# PCB-ENCODER3.net
KiCad netlist of a schematic drawn in EAGLE
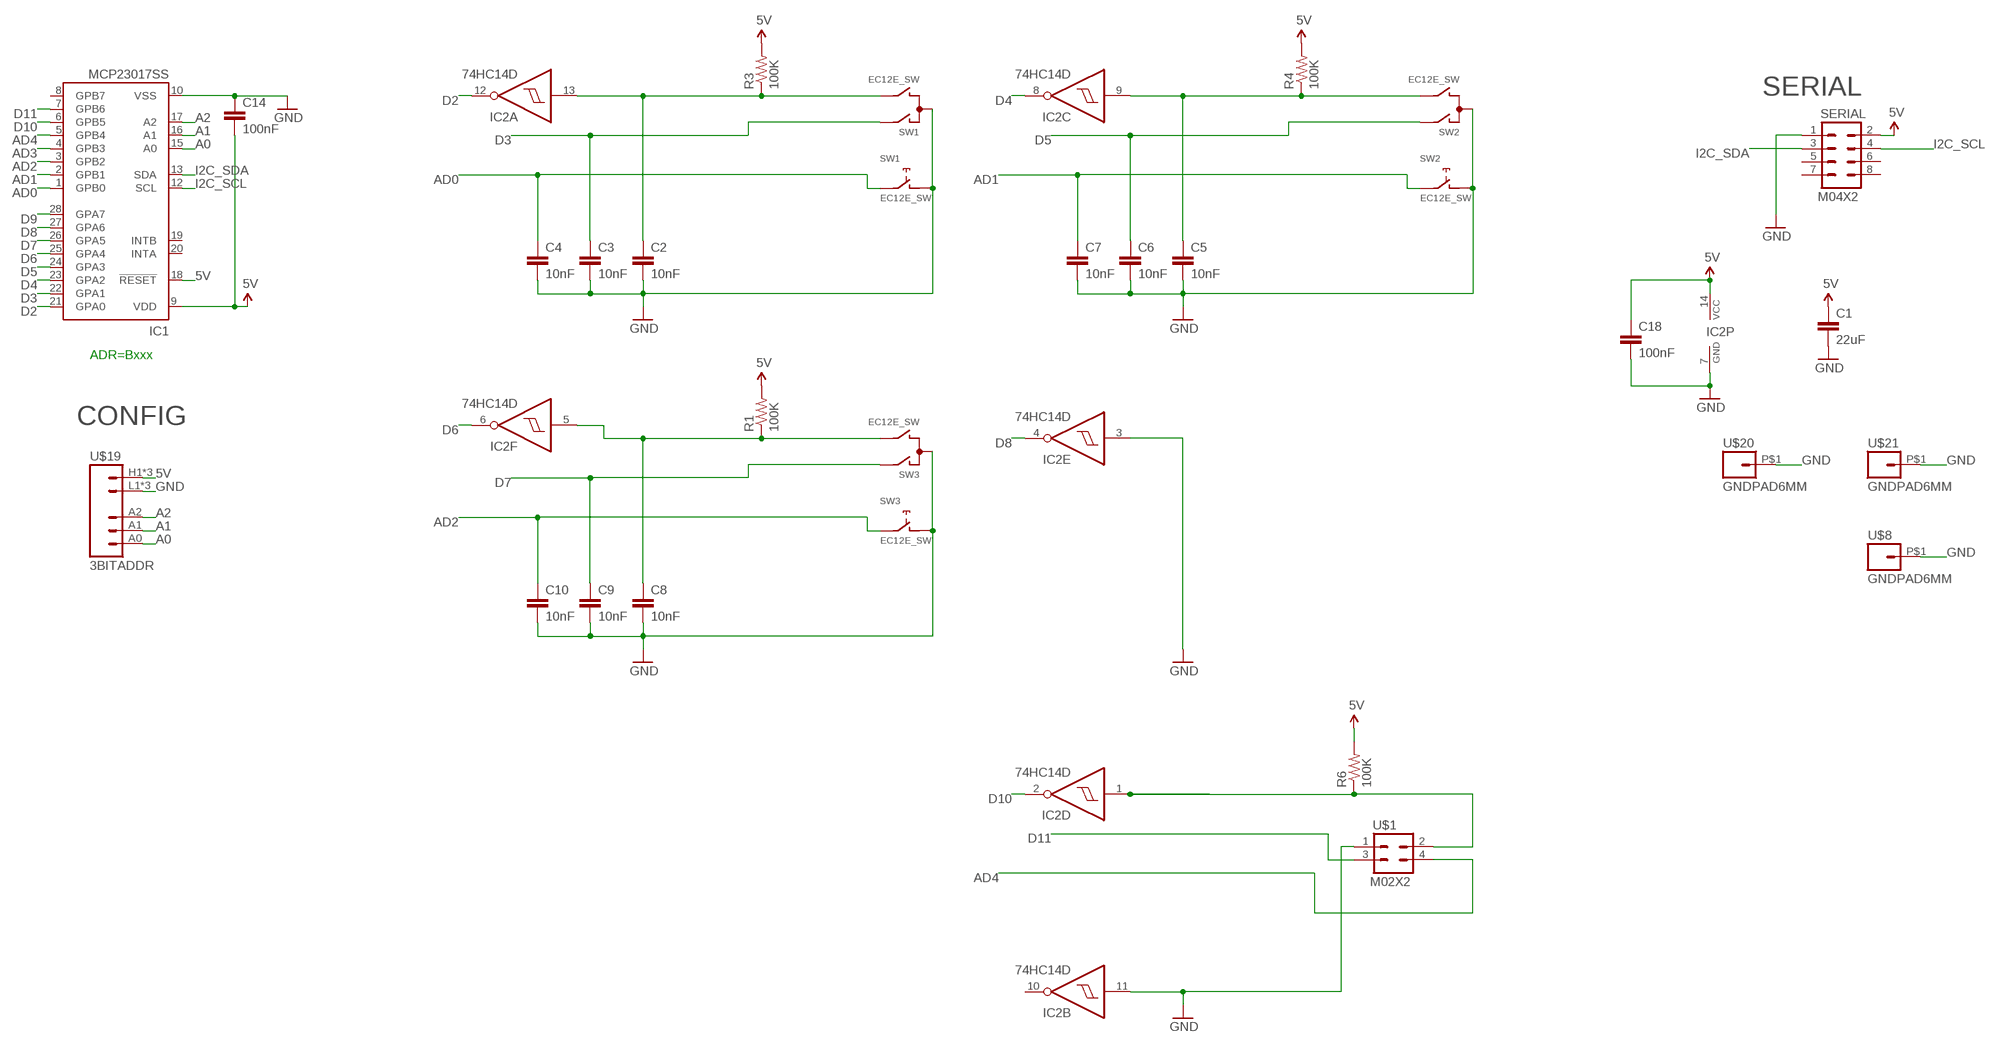
[diagram p0: schematic, sheet 1]

(export (version "E")
  (design (tool "Eeschema 10.0.6"))
  (components
    (comp (ref "C1")
      (value "22uF")
      (footprint "eagle-import:0805")
      (libsource (lib "eagle-import") (part "CAP0805"))
    )
    (comp (ref "C2")
      (value "10nF")
      (footprint "eagle-import:0603-CAP")
      (libsource (lib "eagle-import") (part "CAP0603-CAP"))
    )
    (comp (ref "C3")
      (value "10nF")
      (footprint "eagle-import:0603-CAP")
      (libsource (lib "eagle-import") (part "CAP0603-CAP"))
    )
    (comp (ref "C4")
      (value "10nF")
      (footprint "eagle-import:0603-CAP")
      (libsource (lib "eagle-import") (part "CAP0603-CAP"))
    )
    (comp (ref "C5")
      (value "10nF")
      (footprint "eagle-import:0603-CAP")
      (libsource (lib "eagle-import") (part "CAP0603-CAP"))
    )
    (comp (ref "C6")
      (value "10nF")
      (footprint "eagle-import:0603-CAP")
      (libsource (lib "eagle-import") (part "CAP0603-CAP"))
    )
    (comp (ref "C7")
      (value "10nF")
      (footprint "eagle-import:0603-CAP")
      (libsource (lib "eagle-import") (part "CAP0603-CAP"))
    )
    (comp (ref "C8")
      (value "10nF")
      (footprint "eagle-import:0603-CAP")
      (libsource (lib "eagle-import") (part "CAP0603-CAP"))
    )
    (comp (ref "C9")
      (value "10nF")
      (footprint "eagle-import:0603-CAP")
      (libsource (lib "eagle-import") (part "CAP0603-CAP"))
    )
    (comp (ref "C10")
      (value "10nF")
      (footprint "eagle-import:0603-CAP")
      (libsource (lib "eagle-import") (part "CAP0603-CAP"))
    )
    (comp (ref "C14")
      (value "100nF")
      (footprint "eagle-import:0603-CAP")
      (libsource (lib "eagle-import") (part "CAP0603-CAP"))
    )
    (comp (ref "C18")
      (value "100nF")
      (footprint "eagle-import:0603-CAP")
      (libsource (lib "eagle-import") (part "CAP0603-CAP"))
    )
    (comp (ref "IC1")
      (value "MCP23017SS")
      (footprint "eagle-import:SSOP28")
      (fields
        (field (name "MF") "MICROCHIP")
        (field (name "MPN") "MCP23017-E/SS")
        (field (name "MPN_1") "MCP23017-E/SS")
        (field (name "OC_FARNELL") "1467674")
        (field (name "OC_NEWARK") "31K2960")
      )
      (libsource (lib "eagle-import") (part "MCP23017SS"))
    )
    (comp (ref "IC2")
      (value "74HC14D")
      (footprint "eagle-import:SO14")
      (libsource (lib "eagle-import") (part "7414DHC"))
    )
    (comp (ref "R1")
      (value "100K")
      (footprint "eagle-import:0603-RES")
      (libsource (lib "eagle-import") (part "RESISTOR0603-RES"))
    )
    (comp (ref "R3")
      (value "100K")
      (footprint "eagle-import:0603-RES")
      (libsource (lib "eagle-import") (part "RESISTOR0603-RES"))
    )
    (comp (ref "R4")
      (value "100K")
      (footprint "eagle-import:0603-RES")
      (libsource (lib "eagle-import") (part "RESISTOR0603-RES"))
    )
    (comp (ref "R6")
      (value "100K")
      (footprint "eagle-import:0603-RES")
      (libsource (lib "eagle-import") (part "RESISTOR0603-RES"))
    )
    (comp (ref "SERIAL")
      (value "M04X2")
      (footprint "eagle-import:2X4")
      (libsource (lib "eagle-import") (part "M04X2"))
    )
    (comp (ref "SW1")
      (value "EC12E_SW")
      (footprint "eagle-import:ALPS_EC12E_SW")
      (fields (field (name "MPN") "EC12E2424407"))
      (libsource (lib "eagle-import") (part "EC12E_SW"))
    )
    (comp (ref "SW2")
      (value "EC12E_SW")
      (footprint "eagle-import:ALPS_EC12E_SW")
      (fields (field (name "MPN") "EC12E2424407"))
      (libsource (lib "eagle-import") (part "EC12E_SW"))
    )
    (comp (ref "SW3")
      (value "EC12E_SW")
      (footprint "eagle-import:ALPS_EC12E_SW")
      (fields (field (name "MPN") "EC12E2424407"))
      (libsource (lib "eagle-import") (part "EC12E_SW"))
    )
    (comp (ref "U$1")
      (value "M02X2")
      (footprint "eagle-import:2X2")
      (libsource (lib "eagle-import") (part "M02X2"))
    )
    (comp (ref "U$8")
      (value "GNDPAD6MM")
      (footprint "eagle-import:3.2MMPAD6MM")
      (libsource (lib "eagle-import") (part "GNDPAD6MM"))
    )
    (comp (ref "U$19")
      (value "3BITADDR")
      (footprint "eagle-import:3BITADDR")
      (libsource (lib "eagle-import") (part "3BITADDR"))
    )
    (comp (ref "U$20")
      (value "GNDPAD6MM")
      (footprint "eagle-import:3.2MMPAD6MM")
      (libsource (lib "eagle-import") (part "GNDPAD6MM"))
    )
    (comp (ref "U$21")
      (value "GNDPAD6MM")
      (footprint "eagle-import:3.2MMPAD6MM")
      (libsource (lib "eagle-import") (part "GNDPAD6MM"))
    )
  )
  (nets
    (net (code "1") (name "/A0") (class "Default")
      (node (ref "IC1") (pin "15") (pinfunction "A0_15") (pintype "input"))
      (node (ref "U$19") (pin "A0") (pinfunction "A0_A0") (pintype "passive"))
    )
    (net (code "2") (name "/A1") (class "Default")
      (node (ref "IC1") (pin "16") (pinfunction "A1_16") (pintype "input"))
      (node (ref "U$19") (pin "A1") (pinfunction "A1_A1") (pintype "passive"))
    )
    (net (code "3") (name "/A2") (class "Default")
      (node (ref "IC1") (pin "17") (pinfunction "A2_17") (pintype "input"))
      (node (ref "U$19") (pin "A2") (pinfunction "A2_A2") (pintype "passive"))
    )
    (net (code "4") (name "/AD0") (class "Default")
      (node (ref "C4") (pin "1") (pinfunction "1_1") (pintype "passive"))
      (node (ref "IC1") (pin "1") (pinfunction "GPB0_1") (pintype "bidirectional"))
      (node (ref "SW1") (pin "E") (pinfunction "2_E") (pintype "passive"))
    )
    (net (code "5") (name "/AD1") (class "Default")
      (node (ref "C7") (pin "1") (pinfunction "1_1") (pintype "passive"))
      (node (ref "IC1") (pin "2") (pinfunction "GPB1_2") (pintype "bidirectional"))
      (node (ref "SW2") (pin "E") (pinfunction "2_E") (pintype "passive"))
    )
    (net (code "6") (name "/AD2") (class "Default")
      (node (ref "C10") (pin "1") (pinfunction "1_1") (pintype "passive"))
      (node (ref "IC1") (pin "3") (pinfunction "GPB2_3") (pintype "bidirectional"))
      (node (ref "SW3") (pin "E") (pinfunction "2_E") (pintype "passive"))
    )
    (net (code "7") (name "/AD3") (class "Default")
      (node (ref "IC1") (pin "4") (pinfunction "GPB3_4") (pintype "bidirectional"))
    )
    (net (code "8") (name "/AD4") (class "Default")
      (node (ref "IC1") (pin "5") (pinfunction "GPB4_5") (pintype "bidirectional"))
      (node (ref "U$1") (pin "4") (pinfunction "4_4") (pintype "passive"))
    )
    (net (code "9") (name "/D2") (class "Default")
      (node (ref "IC1") (pin "21") (pinfunction "GPA0_21") (pintype "bidirectional"))
      (node (ref "IC2") (pin "12") (pinfunction "O_12") (pintype "output"))
    )
    (net (code "10") (name "/D3") (class "Default")
      (node (ref "C3") (pin "1") (pinfunction "1_1") (pintype "passive"))
      (node (ref "IC1") (pin "22") (pinfunction "GPA1_22") (pintype "bidirectional"))
      (node (ref "SW1") (pin "A") (pinfunction "A_A") (pintype "passive"))
    )
    (net (code "11") (name "/D4") (class "Default")
      (node (ref "IC1") (pin "23") (pinfunction "GPA2_23") (pintype "bidirectional"))
      (node (ref "IC2") (pin "8") (pinfunction "O_8") (pintype "output"))
    )
    (net (code "12") (name "/D5") (class "Default")
      (node (ref "C6") (pin "1") (pinfunction "1_1") (pintype "passive"))
      (node (ref "IC1") (pin "24") (pinfunction "GPA3_24") (pintype "bidirectional"))
      (node (ref "SW2") (pin "A") (pinfunction "A_A") (pintype "passive"))
    )
    (net (code "13") (name "/D6") (class "Default")
      (node (ref "IC1") (pin "25") (pinfunction "GPA4_25") (pintype "bidirectional"))
      (node (ref "IC2") (pin "6") (pinfunction "O_6") (pintype "output"))
    )
    (net (code "14") (name "/D7") (class "Default")
      (node (ref "C9") (pin "1") (pinfunction "1_1") (pintype "passive"))
      (node (ref "IC1") (pin "26") (pinfunction "GPA5_26") (pintype "bidirectional"))
      (node (ref "SW3") (pin "A") (pinfunction "A_A") (pintype "passive"))
    )
    (net (code "15") (name "/D8") (class "Default")
      (node (ref "IC1") (pin "27") (pinfunction "GPA6_27") (pintype "bidirectional"))
      (node (ref "IC2") (pin "4") (pinfunction "O_4") (pintype "output"))
    )
    (net (code "16") (name "/D9") (class "Default")
      (node (ref "IC1") (pin "28") (pinfunction "GPA7_28") (pintype "bidirectional"))
    )
    (net (code "17") (name "/D10") (class "Default")
      (node (ref "IC1") (pin "6") (pinfunction "GPB5_6") (pintype "bidirectional"))
      (node (ref "IC2") (pin "2") (pinfunction "O_2") (pintype "output"))
    )
    (net (code "18") (name "/D11") (class "Default")
      (node (ref "IC1") (pin "7") (pinfunction "GPB6_7") (pintype "bidirectional"))
      (node (ref "U$1") (pin "3") (pinfunction "3_3") (pintype "passive"))
    )
    (net (code "19") (name "/I2C_SCL") (class "Default")
      (node (ref "IC1") (pin "12") (pinfunction "SCL_12") (pintype "input"))
      (node (ref "SERIAL") (pin "4") (pinfunction "4_4") (pintype "passive"))
    )
    (net (code "20") (name "/I2C_SDA") (class "Default")
      (node (ref "IC1") (pin "13") (pinfunction "SDA_13") (pintype "bidirectional"))
      (node (ref "SERIAL") (pin "3") (pinfunction "3_3") (pintype "passive"))
    )
    (net (code "21") (name "5V") (class "Default")
      (node (ref "C1") (pin "1") (pinfunction "1_1") (pintype "passive"))
      (node (ref "C14") (pin "2") (pinfunction "2_2") (pintype "passive"))
      (node (ref "C18") (pin "1") (pinfunction "1_1") (pintype "passive"))
      (node (ref "IC1") (pin "18") (pinfunction "~{RESET}_18") (pintype "input"))
      (node (ref "IC1") (pin "9") (pinfunction "VDD_9") (pintype "power_in"))
      (node (ref "IC2") (pin "14") (pinfunction "VCC_14") (pintype "power_in"))
      (node (ref "R1") (pin "2") (pinfunction "2_2") (pintype "passive"))
      (node (ref "R3") (pin "2") (pinfunction "2_2") (pintype "passive"))
      (node (ref "R4") (pin "2") (pinfunction "2_2") (pintype "passive"))
      (node (ref "R6") (pin "2") (pinfunction "2_2") (pintype "passive"))
      (node (ref "SERIAL") (pin "2") (pinfunction "2_2") (pintype "passive"))
      (node (ref "U$19") (pin "H1") (pinfunction "VCC_H1") (pintype "passive"))
      (node (ref "U$19") (pin "H2") (pinfunction "VCC_H2") (pintype "passive"))
      (node (ref "U$19") (pin "H3") (pinfunction "VCC_H3") (pintype "passive"))
    )
    (net (code "22") (name "GND") (class "Default")
      (node (ref "C1") (pin "2") (pinfunction "2_2") (pintype "passive"))
      (node (ref "C10") (pin "2") (pinfunction "2_2") (pintype "passive"))
      (node (ref "C14") (pin "1") (pinfunction "1_1") (pintype "passive"))
      (node (ref "C18") (pin "2") (pinfunction "2_2") (pintype "passive"))
      (node (ref "C2") (pin "2") (pinfunction "2_2") (pintype "passive"))
      (node (ref "C3") (pin "2") (pinfunction "2_2") (pintype "passive"))
      (node (ref "C4") (pin "2") (pinfunction "2_2") (pintype "passive"))
      (node (ref "C5") (pin "2") (pinfunction "2_2") (pintype "passive"))
      (node (ref "C6") (pin "2") (pinfunction "2_2") (pintype "passive"))
      (node (ref "C7") (pin "2") (pinfunction "2_2") (pintype "passive"))
      (node (ref "C8") (pin "2") (pinfunction "2_2") (pintype "passive"))
      (node (ref "C9") (pin "2") (pinfunction "2_2") (pintype "passive"))
      (node (ref "IC1") (pin "10") (pinfunction "VSS_10") (pintype "power_in"))
      (node (ref "IC2") (pin "11") (pinfunction "I_11") (pintype "input"))
      (node (ref "IC2") (pin "3") (pinfunction "I_3") (pintype "input"))
      (node (ref "IC2") (pin "7") (pinfunction "GND_7") (pintype "power_in"))
      (node (ref "SERIAL") (pin "1") (pinfunction "1_1") (pintype "passive"))
      (node (ref "SW1") (pin "C") (pinfunction "C_C") (pintype "passive"))
      (node (ref "SW1") (pin "D") (pinfunction "1_D") (pintype "passive"))
      (node (ref "SW2") (pin "C") (pinfunction "C_C") (pintype "passive"))
      (node (ref "SW2") (pin "D") (pinfunction "1_D") (pintype "passive"))
      (node (ref "SW3") (pin "C") (pinfunction "C_C") (pintype "passive"))
      (node (ref "SW3") (pin "D") (pinfunction "1_D") (pintype "passive"))
      (node (ref "U$1") (pin "1") (pinfunction "1_1") (pintype "passive"))
      (node (ref "U$19") (pin "L1") (pinfunction "GND_L1") (pintype "passive"))
      (node (ref "U$19") (pin "L2") (pinfunction "GND_L2") (pintype "passive"))
      (node (ref "U$19") (pin "L3") (pinfunction "GND_L3") (pintype "passive"))
      (node (ref "U$20") (pin "P$1") (pinfunction "1_P$1") (pintype "passive"))
      (node (ref "U$21") (pin "P$1") (pinfunction "1_P$1") (pintype "passive"))
      (node (ref "U$8") (pin "P$1") (pinfunction "1_P$1") (pintype "passive"))
    )
    (net (code "23") (name "Net-(IC2A-I)") (class "Default")
      (node (ref "C2") (pin "1") (pinfunction "1_1") (pintype "passive"))
      (node (ref "IC2") (pin "13") (pinfunction "I_13") (pintype "input"))
      (node (ref "R3") (pin "1") (pinfunction "1_1") (pintype "passive"))
      (node (ref "SW1") (pin "B") (pinfunction "B_B") (pintype "passive"))
    )
    (net (code "24") (name "Net-(IC2C-I)") (class "Default")
      (node (ref "C5") (pin "1") (pinfunction "1_1") (pintype "passive"))
      (node (ref "IC2") (pin "9") (pinfunction "I_9") (pintype "input"))
      (node (ref "R4") (pin "1") (pinfunction "1_1") (pintype "passive"))
      (node (ref "SW2") (pin "B") (pinfunction "B_B") (pintype "passive"))
    )
    (net (code "25") (name "Net-(IC2D-I)") (class "Default")
      (node (ref "IC2") (pin "1") (pinfunction "I_1") (pintype "input"))
      (node (ref "R6") (pin "1") (pinfunction "1_1") (pintype "passive"))
      (node (ref "U$1") (pin "2") (pinfunction "2_2") (pintype "passive"))
    )
    (net (code "26") (name "Net-(IC2F-I)") (class "Default")
      (node (ref "C8") (pin "1") (pinfunction "1_1") (pintype "passive"))
      (node (ref "IC2") (pin "5") (pinfunction "I_5") (pintype "input"))
      (node (ref "R1") (pin "1") (pinfunction "1_1") (pintype "passive"))
      (node (ref "SW3") (pin "B") (pinfunction "B_B") (pintype "passive"))
    )
    (net (code "27") (name "unconnected-(IC1-GPB7-Pad8)") (class "Default")
      (node (ref "IC1") (pin "8") (pinfunction "GPB7_8") (pintype "bidirectional"))
    )
    (net (code "28") (name "unconnected-(IC1-INTA-Pad20)") (class "Default")
      (node (ref "IC1") (pin "20") (pinfunction "INTA_20") (pintype "output"))
    )
    (net (code "29") (name "unconnected-(IC1-INTB-Pad19)") (class "Default")
      (node (ref "IC1") (pin "19") (pinfunction "INTB_19") (pintype "output"))
    )
    (net (code "30") (name "unconnected-(IC2B-O-Pad10)") (class "Default")
      (node (ref "IC2") (pin "10") (pinfunction "O_10") (pintype "output"))
    )
    (net (code "31") (name "unconnected-(SERIAL-Pad5)") (class "Default")
      (node (ref "SERIAL") (pin "5") (pinfunction "5_5") (pintype "passive"))
    )
    (net (code "32") (name "unconnected-(SERIAL-Pad6)") (class "Default")
      (node (ref "SERIAL") (pin "6") (pinfunction "6_6") (pintype "passive"))
    )
    (net (code "33") (name "unconnected-(SERIAL-Pad7)") (class "Default")
      (node (ref "SERIAL") (pin "7") (pinfunction "7_7") (pintype "passive"))
    )
    (net (code "34") (name "unconnected-(SERIAL-Pad8)") (class "Default")
      (node (ref "SERIAL") (pin "8") (pinfunction "8_8") (pintype "passive"))
    )
  )
)
